# 1A20J6_GPS_A.net
KiCad netlist of a schematic drawn in Altium Designer
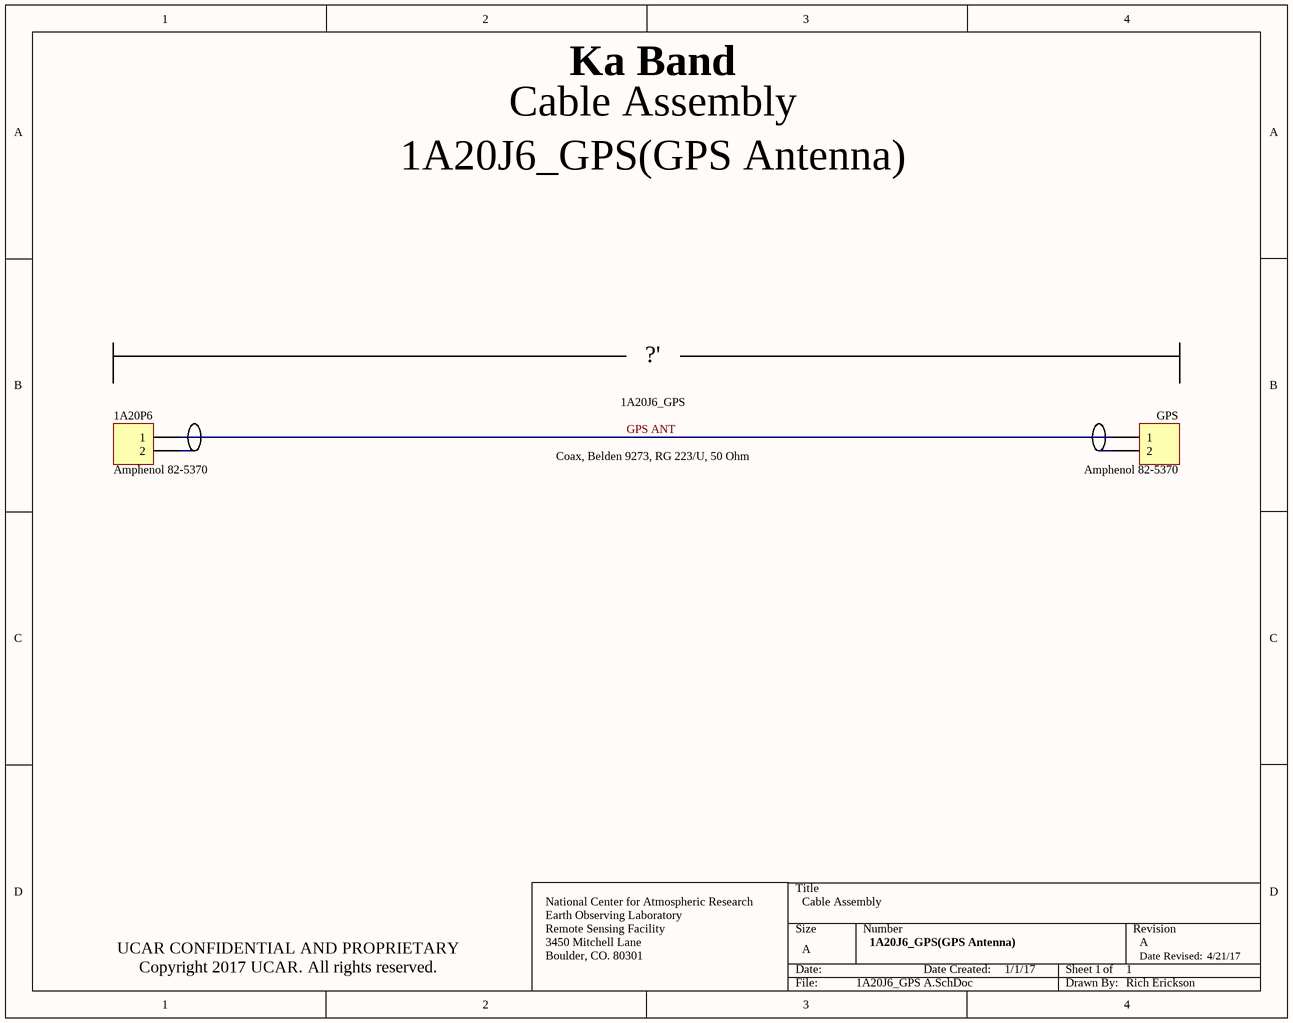
[diagram p0: 1A20J6_GPS A.SchDoc]

(export (version "E")
  (design (tool "Eeschema 10.0.6"))
  (components
    (comp (ref "1A20P6")
      (value "Amphenol 82-5370")
      (footprint "HDR1X2")
      (description "Header, 2-Pin")
      (fields (field (name "PUBLISHER") "Altium Limited"))
      (libsource (lib "Miscellaneous Connectors") (part "Header 2"))
    )
    (comp (ref "GPS")
      (value "Amphenol 82-5370")
      (footprint "HDR1X2")
      (description "Header, 2-Pin")
      (fields (field (name "PUBLISHER") "Altium Limited"))
      (libsource (lib "") (part "Header 2_1"))
    )
  )
  (nets
    (net (code "1") (name "/GPS ANT") (class "Default")
      (node (ref "1A20P6") (pin "1") (pinfunction "1_1") (pintype "passive"))
      (node (ref "GPS") (pin "1") (pinfunction "1_1") (pintype "passive"))
    )
    (net (code "2") (name "unconnected-(1A20P6-Pad2)") (class "Default")
      (node (ref "1A20P6") (pin "2") (pinfunction "2_2") (pintype "passive"))
    )
    (net (code "3") (name "unconnected-(GPS-Pad2)") (class "Default")
      (node (ref "GPS") (pin "2") (pinfunction "2_2") (pintype "passive"))
    )
  )
)
